# Garage_Controller.net
KiCad netlist of a schematic drawn in EAGLE
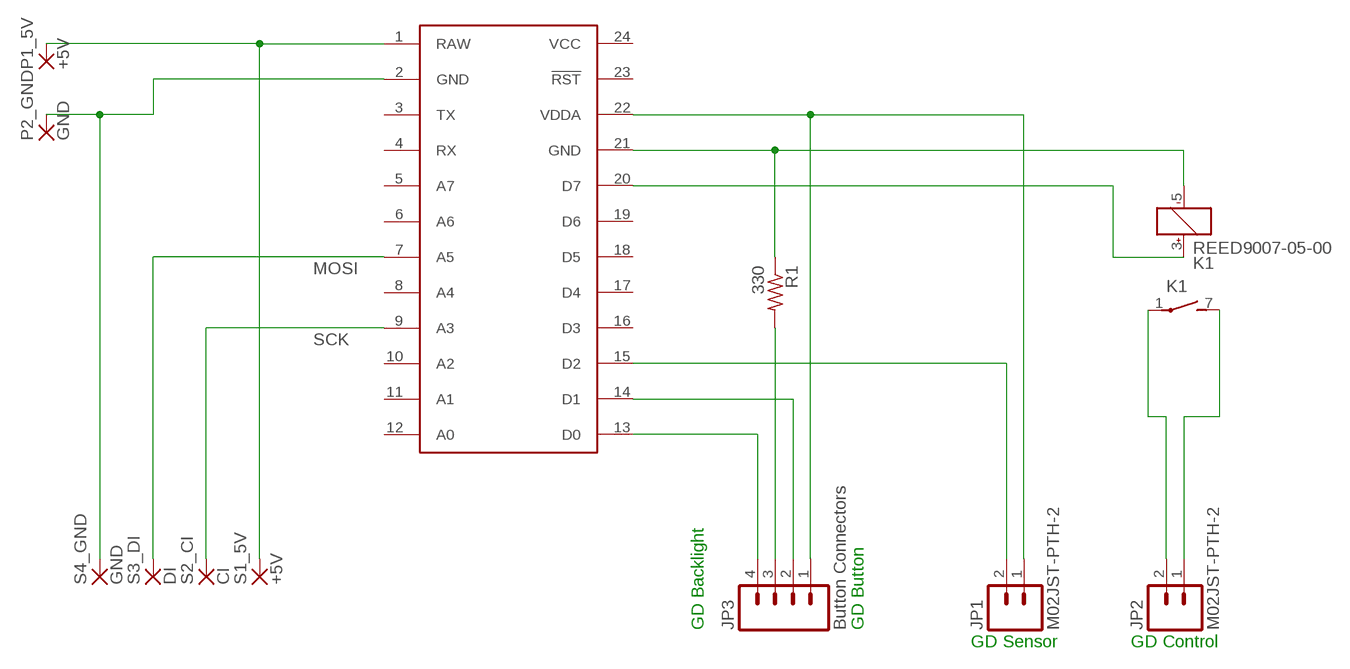
[diagram p0: schematic, sheet 1]

(export (version "E")
  (design (tool "Eeschema 10.0.6"))
  (components
    (comp (ref "CORE")
      (value "SPARK_CORECORE")
      (footprint "eagle-import:SPARK_CORE")
      (libsource (lib "eagle-import") (part "SPARK_CORECORE"))
    )
    (comp (ref "JP1")
      (value "M02JST-PTH-2")
      (footprint "eagle-import:JST-2-PTH")
      (libsource (lib "eagle-import") (part "M02JST-PTH-2"))
    )
    (comp (ref "JP2")
      (value "M02JST-PTH-2")
      (footprint "eagle-import:JST-2-PTH")
      (libsource (lib "eagle-import") (part "M02JST-PTH-2"))
    )
    (comp (ref "JP3")
      (value "Button Connectors")
      (footprint "eagle-import:JST-4-PTH")
      (libsource (lib "eagle-import") (part "M04JST-PTH"))
    )
    (comp (ref "K1")
      (value "REED9007-05-00")
      (footprint "eagle-import:REED")
      (fields (field (name "MPN") "9007-05-00"))
      (libsource (lib "eagle-import") (part "REED9007-05-00"))
    )
    (comp (ref "P1_5V")
      (value "+5V")
      (footprint "eagle-import:1,6_0,8")
      (libsource (lib "eagle-import") (part "1,6/0,8"))
    )
    (comp (ref "P2_GND")
      (value "GND")
      (footprint "eagle-import:1,6_0,8")
      (libsource (lib "eagle-import") (part "1,6/0,8"))
    )
    (comp (ref "R1")
      (value "330")
      (footprint "eagle-import:0207_5V")
      (libsource (lib "eagle-import") (part "R-US_0207/5V"))
    )
    (comp (ref "S1_5V")
      (value "+5V")
      (footprint "eagle-import:1,6_0,8")
      (libsource (lib "eagle-import") (part "1,6/0,8"))
    )
    (comp (ref "S2_CI")
      (value "CI")
      (footprint "eagle-import:1,6_0,8")
      (libsource (lib "eagle-import") (part "1,6/0,8"))
    )
    (comp (ref "S3_DI")
      (value "DI")
      (footprint "eagle-import:1,6_0,8")
      (libsource (lib "eagle-import") (part "1,6/0,8"))
    )
    (comp (ref "S4_GND")
      (value "GND")
      (footprint "eagle-import:1,6_0,8")
      (libsource (lib "eagle-import") (part "1,6/0,8"))
    )
  )
  (nets
    (net (code "1") (name "/MOSI") (class "Default")
      (node (ref "CORE") (pin "7") (pinfunction "A5_7") (pintype "bidirectional"))
      (node (ref "S3_DI") (pin "1") (pinfunction "P_1") (pintype "passive"))
    )
    (net (code "2") (name "/SCK") (class "Default")
      (node (ref "CORE") (pin "9") (pinfunction "A3_9") (pintype "bidirectional"))
      (node (ref "S2_CI") (pin "1") (pinfunction "P_1") (pintype "passive"))
    )
    (net (code "3") (name "/VCC") (class "Default")
      (node (ref "CORE") (pin "24") (pinfunction "VCC_24") (pintype "power_in"))
    )
    (net (code "4") (name "Net-(CORE-D0)") (class "Default")
      (node (ref "CORE") (pin "13") (pinfunction "D0_13") (pintype "bidirectional"))
      (node (ref "JP3") (pin "4") (pinfunction "4_4") (pintype "passive"))
    )
    (net (code "5") (name "Net-(CORE-D1)") (class "Default")
      (node (ref "CORE") (pin "14") (pinfunction "D1_14") (pintype "bidirectional"))
      (node (ref "JP3") (pin "2") (pinfunction "2_2") (pintype "passive"))
    )
    (net (code "6") (name "Net-(CORE-D2)") (class "Default")
      (node (ref "CORE") (pin "15") (pinfunction "D2_15") (pintype "bidirectional"))
      (node (ref "JP1") (pin "2") (pinfunction "2_2") (pintype "passive"))
    )
    (net (code "7") (name "Net-(CORE-D7)") (class "Default")
      (node (ref "CORE") (pin "20") (pinfunction "D7_20") (pintype "bidirectional"))
      (node (ref "K1") (pin "3") (pinfunction "+_3") (pintype "passive"))
    )
    (net (code "8") (name "Net-(CORE-RAW)") (class "Default")
      (node (ref "CORE") (pin "1") (pinfunction "RAW_1") (pintype "power_in"))
      (node (ref "P1_5V") (pin "1") (pinfunction "P_1") (pintype "passive"))
      (node (ref "S1_5V") (pin "1") (pinfunction "P_1") (pintype "passive"))
    )
    (net (code "9") (name "Net-(CORE-VDDA)") (class "Default")
      (node (ref "CORE") (pin "22") (pinfunction "VDDA_22") (pintype "power_in"))
      (node (ref "JP1") (pin "1") (pinfunction "1_1") (pintype "passive"))
      (node (ref "JP3") (pin "1") (pinfunction "1_1") (pintype "passive"))
    )
    (net (code "10") (name "Net-(JP3-Pad3)") (class "Default")
      (node (ref "JP3") (pin "3") (pinfunction "3_3") (pintype "passive"))
      (node (ref "R1") (pin "2") (pinfunction "2_2") (pintype "passive"))
    )
    (net (code "11") (name "Net-(K1A--)") (class "Default")
      (node (ref "CORE") (pin "21") (pinfunction "GND_21") (pintype "power_in"))
      (node (ref "K1") (pin "5") (pinfunction "-_5") (pintype "passive"))
      (node (ref "R1") (pin "1") (pinfunction "1_1") (pintype "passive"))
    )
    (net (code "12") (name "Net-(K1B-P)") (class "Default")
      (node (ref "JP2") (pin "2") (pinfunction "2_2") (pintype "passive"))
      (node (ref "K1") (pin "1") (pinfunction "P_1") (pintype "passive"))
    )
    (net (code "13") (name "Net-(K1B-S)") (class "Default")
      (node (ref "JP2") (pin "1") (pinfunction "1_1") (pintype "passive"))
      (node (ref "K1") (pin "7") (pinfunction "S_7") (pintype "passive"))
    )
    (net (code "14") (name "Net-(P2_GND-P)") (class "Default")
      (node (ref "CORE") (pin "2") (pinfunction "GND_2") (pintype "power_in"))
      (node (ref "P2_GND") (pin "1") (pinfunction "P_1") (pintype "passive"))
      (node (ref "S4_GND") (pin "1") (pinfunction "P_1") (pintype "passive"))
    )
    (net (code "15") (name "unconnected-(CORE-A0-Pad12)") (class "Default")
      (node (ref "CORE") (pin "12") (pinfunction "A0_12") (pintype "bidirectional"))
    )
    (net (code "16") (name "unconnected-(CORE-A1-Pad11)") (class "Default")
      (node (ref "CORE") (pin "11") (pinfunction "A1_11") (pintype "bidirectional"))
    )
    (net (code "17") (name "unconnected-(CORE-A2-Pad10)") (class "Default")
      (node (ref "CORE") (pin "10") (pinfunction "A2_10") (pintype "bidirectional"))
    )
    (net (code "18") (name "unconnected-(CORE-A4-Pad8)") (class "Default")
      (node (ref "CORE") (pin "8") (pinfunction "A4_8") (pintype "bidirectional"))
    )
    (net (code "19") (name "unconnected-(CORE-A6-Pad6)") (class "Default")
      (node (ref "CORE") (pin "6") (pinfunction "A6_6") (pintype "bidirectional"))
    )
    (net (code "20") (name "unconnected-(CORE-A7-Pad5)") (class "Default")
      (node (ref "CORE") (pin "5") (pinfunction "A7_5") (pintype "bidirectional"))
    )
    (net (code "21") (name "unconnected-(CORE-D3-Pad16)") (class "Default")
      (node (ref "CORE") (pin "16") (pinfunction "D3_16") (pintype "bidirectional"))
    )
    (net (code "22") (name "unconnected-(CORE-D4-Pad17)") (class "Default")
      (node (ref "CORE") (pin "17") (pinfunction "D4_17") (pintype "bidirectional"))
    )
    (net (code "23") (name "unconnected-(CORE-D5-Pad18)") (class "Default")
      (node (ref "CORE") (pin "18") (pinfunction "D5_18") (pintype "bidirectional"))
    )
    (net (code "24") (name "unconnected-(CORE-D6-Pad19)") (class "Default")
      (node (ref "CORE") (pin "19") (pinfunction "D6_19") (pintype "bidirectional"))
    )
    (net (code "25") (name "unconnected-(CORE-RX-Pad4)") (class "Default")
      (node (ref "CORE") (pin "4") (pinfunction "RX_4") (pintype "bidirectional"))
    )
    (net (code "26") (name "unconnected-(CORE-TX-Pad3)") (class "Default")
      (node (ref "CORE") (pin "3") (pinfunction "TX_3") (pintype "bidirectional"))
    )
    (net (code "27") (name "unconnected-(CORE-~{RST}-Pad23)") (class "Default")
      (node (ref "CORE") (pin "23") (pinfunction "~{RST}_23") (pintype "bidirectional"))
    )
  )
)
